# phono.net
KiCad netlist of a schematic drawn in EAGLE
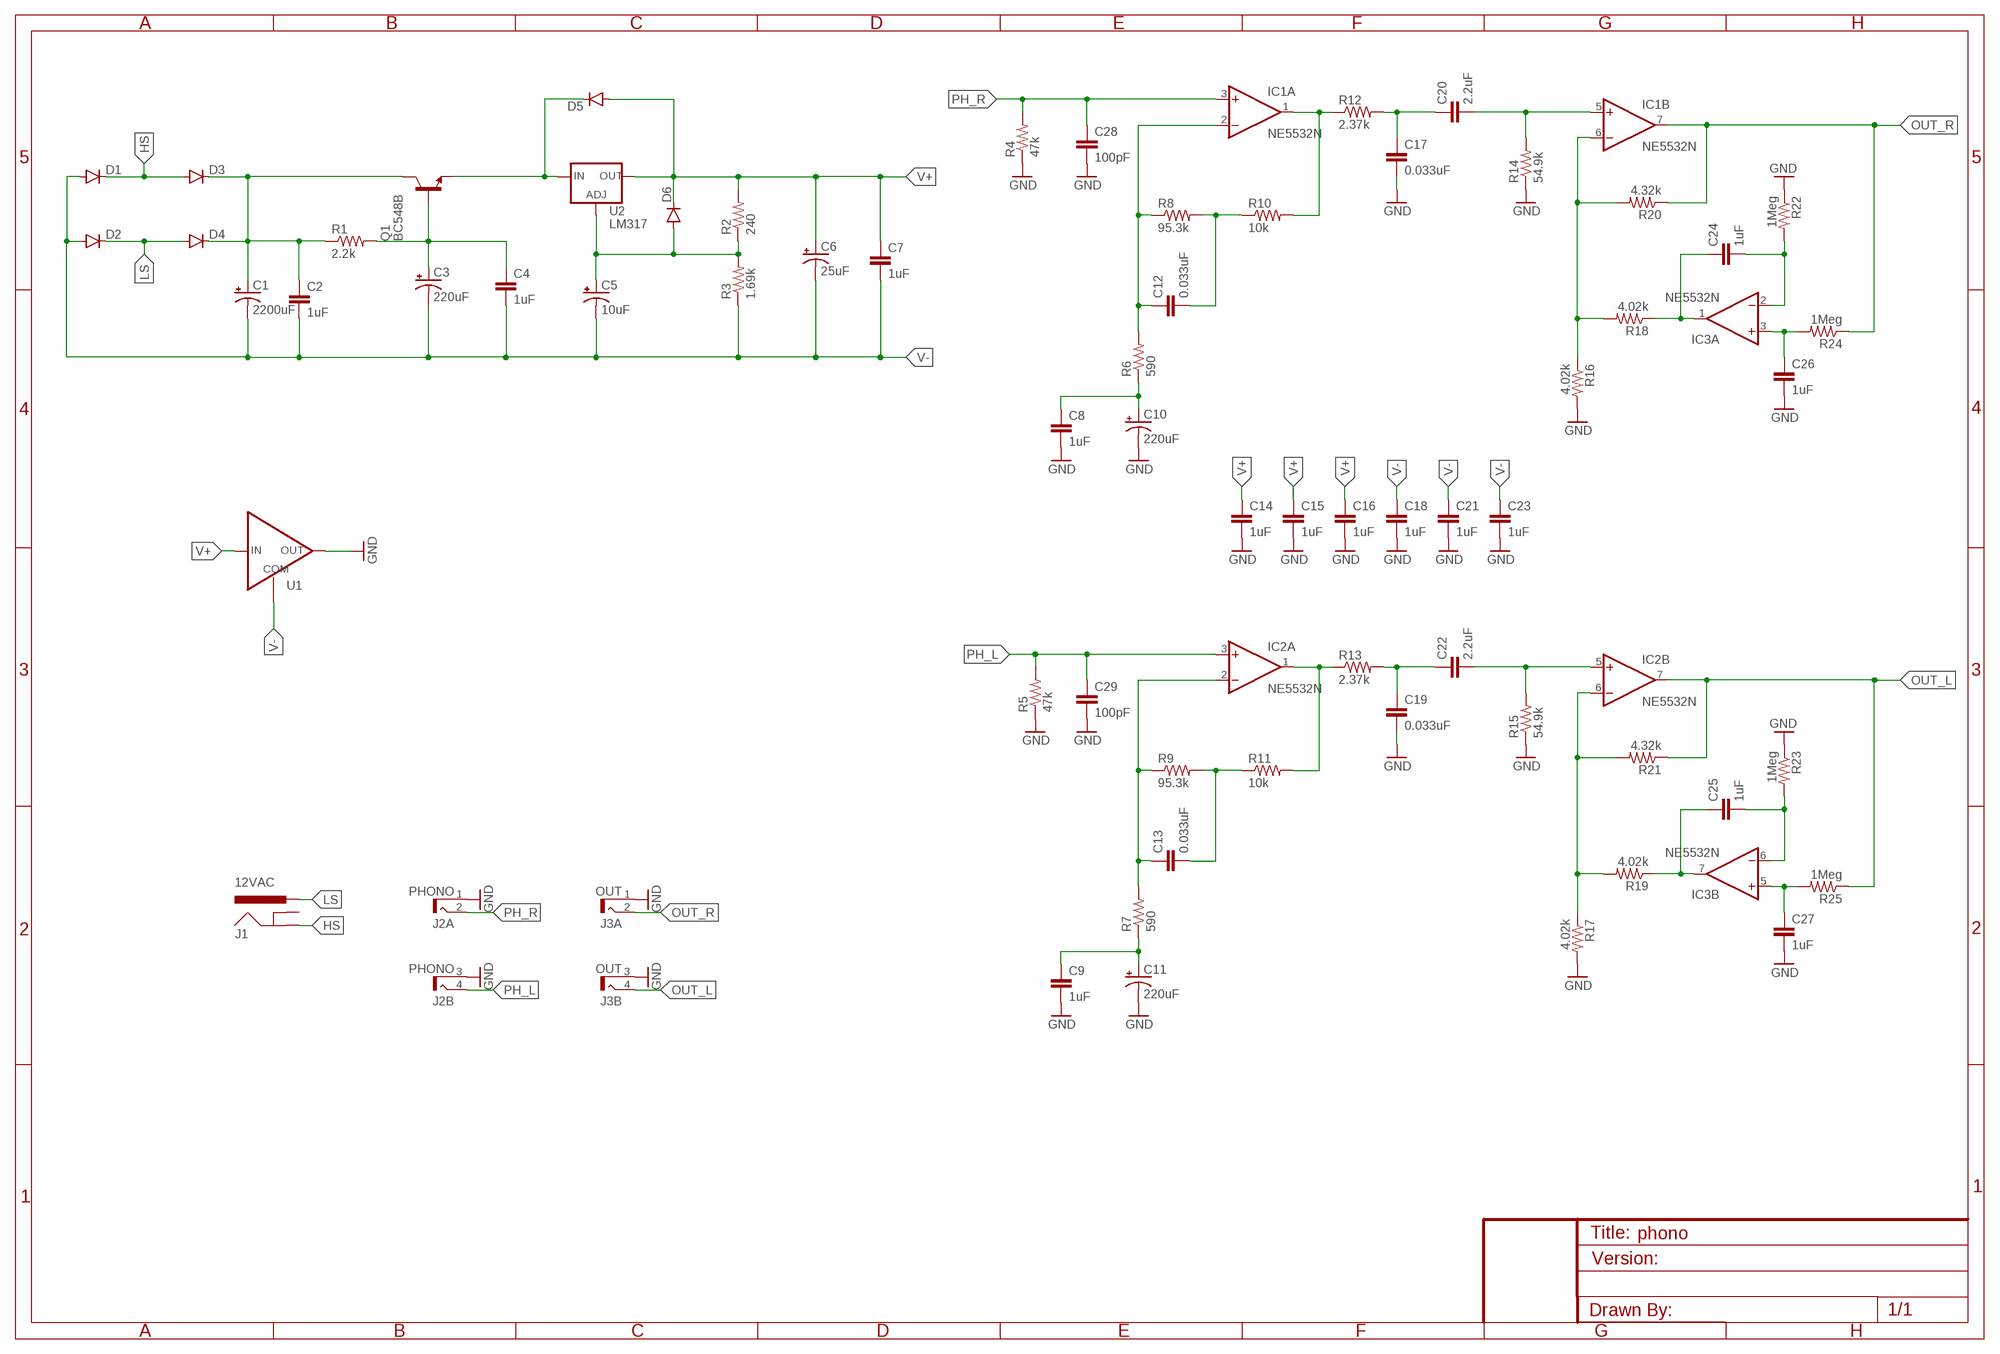
[diagram p0: schematic, sheet 1]

(export (version "E")
  (design (tool "Eeschema 10.0.6"))
  (components
    (comp (ref "C1")
      (value "2200uF")
      (footprint "eagle-import:CPOL-RADIAL-1000UF-25V")
      (libsource (lib "eagle-import") (part "CAP_POLPTH4"))
    )
    (comp (ref "C2")
      (value "1uF")
      (footprint "eagle-import:CAP-PTH-SMALL")
      (libsource (lib "eagle-import") (part "CAPPTH"))
    )
    (comp (ref "C3")
      (value "220uF")
      (footprint "eagle-import:E3,5-8")
      (libsource (lib "eagle-import") (part "CPOL-USE3.5-8"))
    )
    (comp (ref "C4")
      (value "1uF")
      (footprint "eagle-import:CAP-PTH-SMALL")
      (libsource (lib "eagle-import") (part "CAPPTH"))
    )
    (comp (ref "C5")
      (value "10uF")
      (footprint "eagle-import:CPOL-RADIAL-10UF-25V")
      (libsource (lib "eagle-import") (part "CAP_POLPTH2"))
    )
    (comp (ref "C6")
      (value "25uF")
      (footprint "eagle-import:CPOL-RADIAL-10UF-25V")
      (libsource (lib "eagle-import") (part "CAP_POLPTH2"))
    )
    (comp (ref "C7")
      (value "1uF")
      (footprint "eagle-import:CAP-PTH-SMALL")
      (libsource (lib "eagle-import") (part "CAPPTH"))
    )
    (comp (ref "C8")
      (value "1uF")
      (footprint "eagle-import:CAP-PTH-SMALL")
      (libsource (lib "eagle-import") (part "CAPPTH"))
    )
    (comp (ref "C9")
      (value "1uF")
      (footprint "eagle-import:CAP-PTH-SMALL")
      (libsource (lib "eagle-import") (part "CAPPTH"))
    )
    (comp (ref "C10")
      (value "220uF")
      (footprint "eagle-import:E3,5-8")
      (libsource (lib "eagle-import") (part "CPOL-USE3.5-8"))
    )
    (comp (ref "C11")
      (value "220uF")
      (footprint "eagle-import:E3,5-8")
      (libsource (lib "eagle-import") (part "CPOL-USE3.5-8"))
    )
    (comp (ref "C12")
      (value "0.033uF")
      (footprint "eagle-import:C5B7.2")
      (libsource (lib "eagle-import") (part "C5/7.2"))
    )
    (comp (ref "C13")
      (value "0.033uF")
      (footprint "eagle-import:C5B7.2")
      (libsource (lib "eagle-import") (part "C5/7.2"))
    )
    (comp (ref "C14")
      (value "1uF")
      (footprint "eagle-import:CAP-PTH-SMALL")
      (libsource (lib "eagle-import") (part "CAPPTH"))
    )
    (comp (ref "C15")
      (value "1uF")
      (footprint "eagle-import:CAP-PTH-SMALL")
      (libsource (lib "eagle-import") (part "CAPPTH"))
    )
    (comp (ref "C16")
      (value "1uF")
      (footprint "eagle-import:CAP-PTH-SMALL")
      (libsource (lib "eagle-import") (part "CAPPTH"))
    )
    (comp (ref "C17")
      (value "0.033uF")
      (footprint "eagle-import:C5B7.2")
      (libsource (lib "eagle-import") (part "C5/7.2"))
    )
    (comp (ref "C18")
      (value "1uF")
      (footprint "eagle-import:CAP-PTH-SMALL")
      (libsource (lib "eagle-import") (part "CAPPTH"))
    )
    (comp (ref "C19")
      (value "0.033uF")
      (footprint "eagle-import:C5B7.2")
      (libsource (lib "eagle-import") (part "C5/7.2"))
    )
    (comp (ref "C20")
      (value "2.2uF")
      (footprint "eagle-import:C5B7.2")
      (libsource (lib "eagle-import") (part "C5/7.2"))
    )
    (comp (ref "C21")
      (value "1uF")
      (footprint "eagle-import:CAP-PTH-SMALL")
      (libsource (lib "eagle-import") (part "CAPPTH"))
    )
    (comp (ref "C22")
      (value "2.2uF")
      (footprint "eagle-import:C5B7.2")
      (libsource (lib "eagle-import") (part "C5/7.2"))
    )
    (comp (ref "C23")
      (value "1uF")
      (footprint "eagle-import:CAP-PTH-SMALL")
      (libsource (lib "eagle-import") (part "CAPPTH"))
    )
    (comp (ref "C24")
      (value "1uF")
      (footprint "eagle-import:C5B5.5")
      (libsource (lib "eagle-import") (part "C5/5.5"))
    )
    (comp (ref "C25")
      (value "1uF")
      (footprint "eagle-import:C5B5.5")
      (libsource (lib "eagle-import") (part "C5/5.5"))
    )
    (comp (ref "C26")
      (value "1uF")
      (footprint "eagle-import:C5B5.5")
      (libsource (lib "eagle-import") (part "C5/5.5"))
    )
    (comp (ref "C27")
      (value "1uF")
      (footprint "eagle-import:C5B5.5")
      (libsource (lib "eagle-import") (part "C5/5.5"))
    )
    (comp (ref "C28")
      (value "100pF")
      (footprint "eagle-import:C5B4.5")
      (libsource (lib "eagle-import") (part "C5/4.5"))
    )
    (comp (ref "C29")
      (value "100pF")
      (footprint "eagle-import:C5B4.5")
      (libsource (lib "eagle-import") (part "C5/4.5"))
    )
    (comp (ref "D1")
      (value "DIODEPTH")
      (footprint "eagle-import:DIODE-1N4001")
      (libsource (lib "eagle-import") (part "DIODEPTH"))
    )
    (comp (ref "D2")
      (value "DIODEPTH")
      (footprint "eagle-import:DIODE-1N4001")
      (libsource (lib "eagle-import") (part "DIODEPTH"))
    )
    (comp (ref "D3")
      (value "DIODEPTH")
      (footprint "eagle-import:DIODE-1N4001")
      (libsource (lib "eagle-import") (part "DIODEPTH"))
    )
    (comp (ref "D4")
      (value "DIODEPTH")
      (footprint "eagle-import:DIODE-1N4001")
      (libsource (lib "eagle-import") (part "DIODEPTH"))
    )
    (comp (ref "D5")
      (value "DIODEPTH")
      (footprint "eagle-import:DIODE-1N4001")
      (libsource (lib "eagle-import") (part "DIODEPTH"))
    )
    (comp (ref "D6")
      (value "DIODEPTH")
      (footprint "eagle-import:DIODE-1N4001")
      (libsource (lib "eagle-import") (part "DIODEPTH"))
    )
    (comp (ref "IC1")
      (value "NE5532N")
      (footprint "eagle-import:DIL08")
      (libsource (lib "eagle-import") (part "NE5532N"))
    )
    (comp (ref "IC2")
      (value "NE5532N")
      (footprint "eagle-import:DIL08")
      (libsource (lib "eagle-import") (part "NE5532N"))
    )
    (comp (ref "IC3")
      (value "NE5532N")
      (footprint "eagle-import:DIL08")
      (libsource (lib "eagle-import") (part "NE5532N"))
    )
    (comp (ref "J1")
      (value "12VAC")
      (footprint "eagle-import:POWER_JACK_PTH")
      (libsource (lib "eagle-import") (part "POWER_JACKPTH"))
    )
    (comp (ref "J2")
      (value "PHONO")
      (footprint "eagle-import:RCJ-21")
      (libsource (lib "eagle-import") (part "RCJ-21XX"))
    )
    (comp (ref "J3")
      (value "OUT")
      (footprint "eagle-import:RCJ-21")
      (libsource (lib "eagle-import") (part "RCJ-21XX"))
    )
    (comp (ref "Q1")
      (value "BC548B")
      (footprint "eagle-import:TO92-EBC")
      (libsource (lib "eagle-import") (part "BC548B"))
    )
    (comp (ref "R1")
      (value "2.2k")
      (footprint "eagle-import:AXIAL-0.4")
      (libsource (lib "eagle-import") (part "RESISTORPTH-1/4W"))
    )
    (comp (ref "R2")
      (value "240")
      (footprint "eagle-import:AXIAL-0.4")
      (libsource (lib "eagle-import") (part "RESISTORPTH-1/4W"))
    )
    (comp (ref "R3")
      (value "1.69k")
      (footprint "eagle-import:AXIAL-0.4")
      (libsource (lib "eagle-import") (part "RESISTORPTH-1/4W"))
    )
    (comp (ref "R4")
      (value "47k")
      (footprint "eagle-import:AXIAL-0.4")
      (libsource (lib "eagle-import") (part "RESISTORPTH-1/4W"))
    )
    (comp (ref "R5")
      (value "47k")
      (footprint "eagle-import:AXIAL-0.4")
      (libsource (lib "eagle-import") (part "RESISTORPTH-1/4W"))
    )
    (comp (ref "R6")
      (value "590")
      (footprint "eagle-import:AXIAL-0.4")
      (libsource (lib "eagle-import") (part "RESISTORPTH-1/4W"))
    )
    (comp (ref "R7")
      (value "590")
      (footprint "eagle-import:AXIAL-0.4")
      (libsource (lib "eagle-import") (part "RESISTORPTH-1/4W"))
    )
    (comp (ref "R8")
      (value "95.3k")
      (footprint "eagle-import:AXIAL-0.4")
      (libsource (lib "eagle-import") (part "RESISTORPTH-1/4W"))
    )
    (comp (ref "R9")
      (value "95.3k")
      (footprint "eagle-import:AXIAL-0.4")
      (libsource (lib "eagle-import") (part "RESISTORPTH-1/4W"))
    )
    (comp (ref "R10")
      (value "10k")
      (footprint "eagle-import:AXIAL-0.4")
      (libsource (lib "eagle-import") (part "RESISTORPTH-1/4W"))
    )
    (comp (ref "R11")
      (value "10k")
      (footprint "eagle-import:AXIAL-0.4")
      (libsource (lib "eagle-import") (part "RESISTORPTH-1/4W"))
    )
    (comp (ref "R12")
      (value "2.37k")
      (footprint "eagle-import:AXIAL-0.4")
      (libsource (lib "eagle-import") (part "RESISTORPTH-1/4W"))
    )
    (comp (ref "R13")
      (value "2.37k")
      (footprint "eagle-import:AXIAL-0.4")
      (libsource (lib "eagle-import") (part "RESISTORPTH-1/4W"))
    )
    (comp (ref "R14")
      (value "54.9k")
      (footprint "eagle-import:AXIAL-0.4")
      (libsource (lib "eagle-import") (part "RESISTORPTH-1/4W"))
    )
    (comp (ref "R15")
      (value "54.9k")
      (footprint "eagle-import:AXIAL-0.4")
      (libsource (lib "eagle-import") (part "RESISTORPTH-1/4W"))
    )
    (comp (ref "R16")
      (value "4.02k")
      (footprint "eagle-import:AXIAL-0.4")
      (libsource (lib "eagle-import") (part "RESISTORPTH-1/4W"))
    )
    (comp (ref "R17")
      (value "4.02k")
      (footprint "eagle-import:AXIAL-0.4")
      (libsource (lib "eagle-import") (part "RESISTORPTH-1/4W"))
    )
    (comp (ref "R18")
      (value "4.02k")
      (footprint "eagle-import:AXIAL-0.4")
      (libsource (lib "eagle-import") (part "RESISTORPTH-1/4W"))
    )
    (comp (ref "R19")
      (value "4.02k")
      (footprint "eagle-import:AXIAL-0.4")
      (libsource (lib "eagle-import") (part "RESISTORPTH-1/4W"))
    )
    (comp (ref "R20")
      (value "4.32k")
      (footprint "eagle-import:AXIAL-0.4")
      (libsource (lib "eagle-import") (part "RESISTORPTH-1/4W"))
    )
    (comp (ref "R21")
      (value "4.32k")
      (footprint "eagle-import:AXIAL-0.4")
      (libsource (lib "eagle-import") (part "RESISTORPTH-1/4W"))
    )
    (comp (ref "R22")
      (value "1Meg")
      (footprint "eagle-import:AXIAL-0.4")
      (libsource (lib "eagle-import") (part "RESISTORPTH-1/4W"))
    )
    (comp (ref "R23")
      (value "1Meg")
      (footprint "eagle-import:AXIAL-0.4")
      (libsource (lib "eagle-import") (part "RESISTORPTH-1/4W"))
    )
    (comp (ref "R24")
      (value "1Meg")
      (footprint "eagle-import:AXIAL-0.4")
      (libsource (lib "eagle-import") (part "RESISTORPTH-1/4W"))
    )
    (comp (ref "R25")
      (value "1Meg")
      (footprint "eagle-import:AXIAL-0.4")
      (libsource (lib "eagle-import") (part "RESISTORPTH-1/4W"))
    )
    (comp (ref "U1")
      (value "TLE2426-3")
      (footprint "eagle-import:TO92-BENT")
      (libsource (lib "eagle-import") (part "TLE2426-3"))
    )
    (comp (ref "U2")
      (value "LM317")
      (footprint "eagle-import:V-REG_DPACK")
      (libsource (lib "eagle-import") (part "V_REG_317DPACK"))
    )
  )
  (nets
    (net (code "1") (name "GND") (class "Default")
      (node (ref "C10") (pin "-") (pinfunction "-_-") (pintype "passive"))
      (node (ref "C11") (pin "-") (pinfunction "-_-") (pintype "passive"))
      (node (ref "C14") (pin "2") (pinfunction "2_2") (pintype "passive"))
      (node (ref "C15") (pin "2") (pinfunction "2_2") (pintype "passive"))
      (node (ref "C16") (pin "2") (pinfunction "2_2") (pintype "passive"))
      (node (ref "C17") (pin "2") (pinfunction "2_2") (pintype "passive"))
      (node (ref "C18") (pin "2") (pinfunction "2_2") (pintype "passive"))
      (node (ref "C19") (pin "2") (pinfunction "2_2") (pintype "passive"))
      (node (ref "C21") (pin "2") (pinfunction "2_2") (pintype "passive"))
      (node (ref "C23") (pin "2") (pinfunction "2_2") (pintype "passive"))
      (node (ref "C26") (pin "2") (pinfunction "2_2") (pintype "passive"))
      (node (ref "C27") (pin "2") (pinfunction "2_2") (pintype "passive"))
      (node (ref "C28") (pin "2") (pinfunction "2_2") (pintype "passive"))
      (node (ref "C29") (pin "2") (pinfunction "2_2") (pintype "passive"))
      (node (ref "C8") (pin "2") (pinfunction "2_2") (pintype "passive"))
      (node (ref "C9") (pin "2") (pinfunction "2_2") (pintype "passive"))
      (node (ref "J2") (pin "1") (pinfunction "S_1") (pintype "passive"))
      (node (ref "J2") (pin "3") (pinfunction "S_3") (pintype "passive"))
      (node (ref "J3") (pin "1") (pinfunction "S_1") (pintype "passive"))
      (node (ref "J3") (pin "3") (pinfunction "S_3") (pintype "passive"))
      (node (ref "R14") (pin "P$1") (pinfunction "1_P$1") (pintype "passive"))
      (node (ref "R15") (pin "P$1") (pinfunction "1_P$1") (pintype "passive"))
      (node (ref "R16") (pin "P$2") (pinfunction "2_P$2") (pintype "passive"))
      (node (ref "R17") (pin "P$2") (pinfunction "2_P$2") (pintype "passive"))
      (node (ref "R22") (pin "P$1") (pinfunction "1_P$1") (pintype "passive"))
      (node (ref "R23") (pin "P$1") (pinfunction "1_P$1") (pintype "passive"))
      (node (ref "R4") (pin "P$1") (pinfunction "1_P$1") (pintype "passive"))
      (node (ref "R5") (pin "P$1") (pinfunction "1_P$1") (pintype "passive"))
      (node (ref "U1") (pin "1") (pinfunction "OUT_1") (pintype "output"))
    )
    (net (code "2") (name "HS") (class "Default")
      (node (ref "D1") (pin "C") (pinfunction "C_C") (pintype "passive"))
      (node (ref "D3") (pin "A") (pinfunction "A_A") (pintype "passive"))
      (node (ref "J1") (pin "GND") (pinfunction "GND_GND") (pintype "bidirectional"))
    )
    (net (code "3") (name "LS") (class "Default")
      (node (ref "D2") (pin "C") (pinfunction "C_C") (pintype "passive"))
      (node (ref "D4") (pin "A") (pinfunction "A_A") (pintype "passive"))
      (node (ref "J1") (pin "PWR") (pinfunction "PWR_PWR") (pintype "bidirectional"))
    )
    (net (code "4") (name "Net-(C5-+)") (class "Default")
      (node (ref "C5") (pin "1") (pinfunction "+_1") (pintype "passive"))
      (node (ref "D6") (pin "A") (pinfunction "A_A") (pintype "passive"))
      (node (ref "R2") (pin "P$1") (pinfunction "1_P$1") (pintype "passive"))
      (node (ref "R3") (pin "P$2") (pinfunction "2_P$2") (pintype "passive"))
      (node (ref "U2") (pin "1") (pinfunction "ADJ_1") (pintype "input"))
    )
    (net (code "5") (name "Net-(IC1A--IN)") (class "Default")
      (node (ref "C12") (pin "1") (pinfunction "1_1") (pintype "passive"))
      (node (ref "IC1") (pin "2") (pinfunction "-IN_2") (pintype "input"))
      (node (ref "R6") (pin "P$2") (pinfunction "2_P$2") (pintype "passive"))
      (node (ref "R8") (pin "P$1") (pinfunction "1_P$1") (pintype "passive"))
    )
    (net (code "6") (name "Net-(IC1A-OUT)") (class "Default")
      (node (ref "IC1") (pin "1") (pinfunction "OUT_1") (pintype "output"))
      (node (ref "R10") (pin "P$2") (pinfunction "2_P$2") (pintype "passive"))
      (node (ref "R12") (pin "P$1") (pinfunction "1_P$1") (pintype "passive"))
    )
    (net (code "7") (name "Net-(IC1B-+IN)") (class "Default")
      (node (ref "C20") (pin "2") (pinfunction "2_2") (pintype "passive"))
      (node (ref "IC1") (pin "5") (pinfunction "+IN_5") (pintype "input"))
      (node (ref "R14") (pin "P$2") (pinfunction "2_P$2") (pintype "passive"))
    )
    (net (code "8") (name "Net-(IC1B--IN)") (class "Default")
      (node (ref "IC1") (pin "6") (pinfunction "-IN_6") (pintype "input"))
      (node (ref "R16") (pin "P$1") (pinfunction "1_P$1") (pintype "passive"))
      (node (ref "R18") (pin "P$2") (pinfunction "2_P$2") (pintype "passive"))
      (node (ref "R20") (pin "P$2") (pinfunction "2_P$2") (pintype "passive"))
    )
    (net (code "9") (name "Net-(IC2A--IN)") (class "Default")
      (node (ref "C13") (pin "1") (pinfunction "1_1") (pintype "passive"))
      (node (ref "IC2") (pin "2") (pinfunction "-IN_2") (pintype "input"))
      (node (ref "R7") (pin "P$2") (pinfunction "2_P$2") (pintype "passive"))
      (node (ref "R9") (pin "P$1") (pinfunction "1_P$1") (pintype "passive"))
    )
    (net (code "10") (name "Net-(IC2A-OUT)") (class "Default")
      (node (ref "IC2") (pin "1") (pinfunction "OUT_1") (pintype "output"))
      (node (ref "R11") (pin "P$2") (pinfunction "2_P$2") (pintype "passive"))
      (node (ref "R13") (pin "P$1") (pinfunction "1_P$1") (pintype "passive"))
    )
    (net (code "11") (name "Net-(IC2B-+IN)") (class "Default")
      (node (ref "C22") (pin "2") (pinfunction "2_2") (pintype "passive"))
      (node (ref "IC2") (pin "5") (pinfunction "+IN_5") (pintype "input"))
      (node (ref "R15") (pin "P$2") (pinfunction "2_P$2") (pintype "passive"))
    )
    (net (code "12") (name "Net-(IC2B--IN)") (class "Default")
      (node (ref "IC2") (pin "6") (pinfunction "-IN_6") (pintype "input"))
      (node (ref "R17") (pin "P$1") (pinfunction "1_P$1") (pintype "passive"))
      (node (ref "R19") (pin "P$2") (pinfunction "2_P$2") (pintype "passive"))
      (node (ref "R21") (pin "P$2") (pinfunction "2_P$2") (pintype "passive"))
    )
    (net (code "13") (name "Net-(IC3A-+IN)") (class "Default")
      (node (ref "C26") (pin "1") (pinfunction "1_1") (pintype "passive"))
      (node (ref "IC3") (pin "3") (pinfunction "+IN_3") (pintype "input"))
      (node (ref "R24") (pin "P$2") (pinfunction "2_P$2") (pintype "passive"))
    )
    (net (code "14") (name "Net-(IC3A--IN)") (class "Default")
      (node (ref "C24") (pin "2") (pinfunction "2_2") (pintype "passive"))
      (node (ref "IC3") (pin "2") (pinfunction "-IN_2") (pintype "input"))
      (node (ref "R22") (pin "P$2") (pinfunction "2_P$2") (pintype "passive"))
    )
    (net (code "15") (name "Net-(IC3A-OUT)") (class "Default")
      (node (ref "C24") (pin "1") (pinfunction "1_1") (pintype "passive"))
      (node (ref "IC3") (pin "1") (pinfunction "OUT_1") (pintype "output"))
      (node (ref "R18") (pin "P$1") (pinfunction "1_P$1") (pintype "passive"))
    )
    (net (code "16") (name "Net-(IC3B-+IN)") (class "Default")
      (node (ref "C27") (pin "1") (pinfunction "1_1") (pintype "passive"))
      (node (ref "IC3") (pin "5") (pinfunction "+IN_5") (pintype "input"))
      (node (ref "R25") (pin "P$2") (pinfunction "2_P$2") (pintype "passive"))
    )
    (net (code "17") (name "Net-(IC3B--IN)") (class "Default")
      (node (ref "C25") (pin "2") (pinfunction "2_2") (pintype "passive"))
      (node (ref "IC3") (pin "6") (pinfunction "-IN_6") (pintype "input"))
      (node (ref "R23") (pin "P$2") (pinfunction "2_P$2") (pintype "passive"))
    )
    (net (code "18") (name "Net-(IC3B-OUT)") (class "Default")
      (node (ref "C25") (pin "1") (pinfunction "1_1") (pintype "passive"))
      (node (ref "IC3") (pin "7") (pinfunction "OUT_7") (pintype "output"))
      (node (ref "R19") (pin "P$1") (pinfunction "1_P$1") (pintype "passive"))
    )
    (net (code "19") (name "Net-(R1-1)") (class "Default")
      (node (ref "C1") (pin "+") (pinfunction "+_+") (pintype "passive"))
      (node (ref "C2") (pin "1") (pinfunction "1_1") (pintype "passive"))
      (node (ref "D3") (pin "C") (pinfunction "C_C") (pintype "passive"))
      (node (ref "D4") (pin "C") (pinfunction "C_C") (pintype "passive"))
      (node (ref "Q1") (pin "C") (pinfunction "C_C") (pintype "passive"))
      (node (ref "R1") (pin "P$1") (pinfunction "1_P$1") (pintype "passive"))
    )
    (net (code "20") (name "Net-(R1-2)") (class "Default")
      (node (ref "C3") (pin "+") (pinfunction "+_+") (pintype "passive"))
      (node (ref "C4") (pin "1") (pinfunction "1_1") (pintype "passive"))
      (node (ref "Q1") (pin "B") (pinfunction "B_B") (pintype "passive"))
      (node (ref "R1") (pin "P$2") (pinfunction "2_P$2") (pintype "passive"))
    )
    (net (code "21") (name "Net-(R6-1)") (class "Default")
      (node (ref "C10") (pin "+") (pinfunction "+_+") (pintype "passive"))
      (node (ref "C8") (pin "1") (pinfunction "1_1") (pintype "passive"))
      (node (ref "R6") (pin "P$1") (pinfunction "1_P$1") (pintype "passive"))
    )
    (net (code "22") (name "Net-(R7-1)") (class "Default")
      (node (ref "C11") (pin "+") (pinfunction "+_+") (pintype "passive"))
      (node (ref "C9") (pin "1") (pinfunction "1_1") (pintype "passive"))
      (node (ref "R7") (pin "P$1") (pinfunction "1_P$1") (pintype "passive"))
    )
    (net (code "23") (name "Net-(R10-1)") (class "Default")
      (node (ref "C12") (pin "2") (pinfunction "2_2") (pintype "passive"))
      (node (ref "R10") (pin "P$1") (pinfunction "1_P$1") (pintype "passive"))
      (node (ref "R8") (pin "P$2") (pinfunction "2_P$2") (pintype "passive"))
    )
    (net (code "24") (name "Net-(R11-1)") (class "Default")
      (node (ref "C13") (pin "2") (pinfunction "2_2") (pintype "passive"))
      (node (ref "R11") (pin "P$1") (pinfunction "1_P$1") (pintype "passive"))
      (node (ref "R9") (pin "P$2") (pinfunction "2_P$2") (pintype "passive"))
    )
    (net (code "25") (name "Net-(R12-2)") (class "Default")
      (node (ref "C17") (pin "1") (pinfunction "1_1") (pintype "passive"))
      (node (ref "C20") (pin "1") (pinfunction "1_1") (pintype "passive"))
      (node (ref "R12") (pin "P$2") (pinfunction "2_P$2") (pintype "passive"))
    )
    (net (code "26") (name "Net-(R13-2)") (class "Default")
      (node (ref "C19") (pin "1") (pinfunction "1_1") (pintype "passive"))
      (node (ref "C22") (pin "1") (pinfunction "1_1") (pintype "passive"))
      (node (ref "R13") (pin "P$2") (pinfunction "2_P$2") (pintype "passive"))
    )
    (net (code "27") (name "Net-(U2-IN)") (class "Default")
      (node (ref "D5") (pin "C") (pinfunction "C_C") (pintype "passive"))
      (node (ref "Q1") (pin "E") (pinfunction "E_E") (pintype "passive"))
      (node (ref "U2") (pin "3") (pinfunction "IN_3") (pintype "input"))
    )
    (net (code "28") (name "OUT_L") (class "Default")
      (node (ref "IC2") (pin "7") (pinfunction "OUT_7") (pintype "output"))
      (node (ref "J3") (pin "4") (pinfunction "T_4") (pintype "passive"))
      (node (ref "R21") (pin "P$1") (pinfunction "1_P$1") (pintype "passive"))
      (node (ref "R25") (pin "P$1") (pinfunction "1_P$1") (pintype "passive"))
    )
    (net (code "29") (name "OUT_R") (class "Default")
      (node (ref "IC1") (pin "7") (pinfunction "OUT_7") (pintype "output"))
      (node (ref "J3") (pin "2") (pinfunction "T_2") (pintype "passive"))
      (node (ref "R20") (pin "P$1") (pinfunction "1_P$1") (pintype "passive"))
      (node (ref "R24") (pin "P$1") (pinfunction "1_P$1") (pintype "passive"))
    )
    (net (code "30") (name "PH_L") (class "Default")
      (node (ref "C29") (pin "1") (pinfunction "1_1") (pintype "passive"))
      (node (ref "IC2") (pin "3") (pinfunction "+IN_3") (pintype "input"))
      (node (ref "J2") (pin "4") (pinfunction "T_4") (pintype "passive"))
      (node (ref "R5") (pin "P$2") (pinfunction "2_P$2") (pintype "passive"))
    )
    (net (code "31") (name "PH_R") (class "Default")
      (node (ref "C28") (pin "1") (pinfunction "1_1") (pintype "passive"))
      (node (ref "IC1") (pin "3") (pinfunction "+IN_3") (pintype "input"))
      (node (ref "J2") (pin "2") (pinfunction "T_2") (pintype "passive"))
      (node (ref "R4") (pin "P$2") (pinfunction "2_P$2") (pintype "passive"))
    )
    (net (code "32") (name "V+") (class "Default")
      (node (ref "C14") (pin "1") (pinfunction "1_1") (pintype "passive"))
      (node (ref "C15") (pin "1") (pinfunction "1_1") (pintype "passive"))
      (node (ref "C16") (pin "1") (pinfunction "1_1") (pintype "passive"))
      (node (ref "C6") (pin "1") (pinfunction "+_1") (pintype "passive"))
      (node (ref "C7") (pin "1") (pinfunction "1_1") (pintype "passive"))
      (node (ref "D5") (pin "A") (pinfunction "A_A") (pintype "passive"))
      (node (ref "D6") (pin "C") (pinfunction "C_C") (pintype "passive"))
      (node (ref "R2") (pin "P$2") (pinfunction "2_P$2") (pintype "passive"))
      (node (ref "U1") (pin "3") (pinfunction "IN_3") (pintype "input"))
      (node (ref "U2") (pin "4") (pinfunction "OUT_4") (pintype "output"))
    )
    (net (code "33") (name "V-") (class "Default")
      (node (ref "C1") (pin "-") (pinfunction "-_-") (pintype "passive"))
      (node (ref "C18") (pin "1") (pinfunction "1_1") (pintype "passive"))
      (node (ref "C2") (pin "2") (pinfunction "2_2") (pintype "passive"))
      (node (ref "C21") (pin "1") (pinfunction "1_1") (pintype "passive"))
      (node (ref "C23") (pin "1") (pinfunction "1_1") (pintype "passive"))
      (node (ref "C3") (pin "-") (pinfunction "-_-") (pintype "passive"))
      (node (ref "C4") (pin "2") (pinfunction "2_2") (pintype "passive"))
      (node (ref "C5") (pin "2") (pinfunction "-_2") (pintype "passive"))
      (node (ref "C6") (pin "2") (pinfunction "-_2") (pintype "passive"))
      (node (ref "C7") (pin "2") (pinfunction "2_2") (pintype "passive"))
      (node (ref "D1") (pin "A") (pinfunction "A_A") (pintype "passive"))
      (node (ref "D2") (pin "A") (pinfunction "A_A") (pintype "passive"))
      (node (ref "R3") (pin "P$1") (pinfunction "1_P$1") (pintype "passive"))
      (node (ref "U1") (pin "2") (pinfunction "COM_2") (pintype "input"))
    )
    (net (code "34") (name "unconnected-(J1-PadGNDBREAK)") (class "Default")
      (node (ref "J1") (pin "GNDBREAK") (pinfunction "GNDBREAK_GNDBREAK") (pintype "bidirectional"))
    )
  )
)
